# SwitchedPowerAdapter.net
KiCad netlist of a schematic drawn in EAGLE
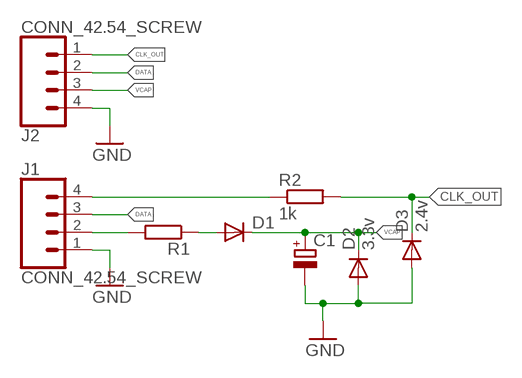
[diagram p0: schematic, sheet 1]

(export (version "E")
  (design (tool "Eeschema 10.0.6"))
  (components
    (comp (ref "C1")
      (value "CPOL-EUHL")
      (footprint "eagle-import:HL")
      (libsource (lib "eagle-import") (part "CPOL-EUHL"))
    )
    (comp (ref "D1")
      (value "DIODEDO-214AC")
      (footprint "eagle-import:DO214AC")
      (fields
        (field (name "DIGIKEY") "S1AFSCT-ND")
        (field (name "MF") "On Semiconductor")
        (field (name "MPN") "S1A")
      )
      (libsource (lib "eagle-import") (part "DIODEDO-214AC"))
    )
    (comp (ref "D2")
      (value "3.3v")
      (footprint "eagle-import:SOD-123")
      (fields (field (name "MF") "Vishay") (field (name "MPN") "MMSZ4683-HE3-08"))
      (libsource (lib "eagle-import") (part "DIODESOD-123"))
    )
    (comp (ref "D3")
      (value "2.4v")
      (footprint "eagle-import:SOD-123")
      (libsource (lib "eagle-import") (part "DIODESOD-123"))
    )
    (comp (ref "J1")
      (value "CONN_42.54_SCREW")
      (footprint "eagle-import:1X04_SCREW")
      (fields (field (name "MF") "On Shore") (field (name "MPN") "OSTVN04A150"))
      (libsource (lib "eagle-import") (part "CONN_42.54_SCREW"))
    )
    (comp (ref "J2")
      (value "CONN_42.54_SCREW")
      (footprint "eagle-import:1X04_SCREW")
      (fields (field (name "MF") "On Shore") (field (name "MPN") "OSTVN04A150"))
      (libsource (lib "eagle-import") (part "CONN_42.54_SCREW"))
    )
    (comp (ref "R1")
      (value "R-EU_R2512")
      (footprint "eagle-import:R2512")
      (libsource (lib "eagle-import") (part "R-EU_R2512"))
    )
    (comp (ref "R2")
      (value "1k")
      (footprint "eagle-import:R0402")
      (fields (field (name "MF") "Yageo"))
      (libsource (lib "eagle-import") (part "R-EU_R0402"))
    )
  )
  (nets
    (net (code "1") (name "CLK_OUT") (class "Default")
      (node (ref "D3") (pin "CAT") (pinfunction "C_CAT") (pintype "passive"))
      (node (ref "J2") (pin "1") (pinfunction "1_1") (pintype "passive"))
      (node (ref "R2") (pin "2") (pinfunction "2_2") (pintype "passive"))
    )
    (net (code "2") (name "DATA") (class "Default")
      (node (ref "J1") (pin "3") (pinfunction "3_3") (pintype "passive"))
      (node (ref "J2") (pin "2") (pinfunction "2_2") (pintype "passive"))
    )
    (net (code "3") (name "GND") (class "Default")
      (node (ref "C1") (pin "-") (pinfunction "-_-") (pintype "passive"))
      (node (ref "D2") (pin "ANODE") (pinfunction "A_ANODE") (pintype "passive"))
      (node (ref "D3") (pin "ANODE") (pinfunction "A_ANODE") (pintype "passive"))
      (node (ref "J1") (pin "1") (pinfunction "1_1") (pintype "passive"))
      (node (ref "J2") (pin "4") (pinfunction "4_4") (pintype "passive"))
    )
    (net (code "4") (name "Net-(D1-PadA)") (class "Default")
      (node (ref "D1") (pin "A") (pinfunction "A_A") (pintype "passive"))
      (node (ref "R1") (pin "1") (pinfunction "1_1") (pintype "passive"))
    )
    (net (code "5") (name "Net-(J1-Pad2)") (class "Default")
      (node (ref "J1") (pin "2") (pinfunction "2_2") (pintype "passive"))
      (node (ref "R1") (pin "2") (pinfunction "2_2") (pintype "passive"))
    )
    (net (code "6") (name "Net-(J1-Pad4)") (class "Default")
      (node (ref "J1") (pin "4") (pinfunction "4_4") (pintype "passive"))
      (node (ref "R2") (pin "1") (pinfunction "1_1") (pintype "passive"))
    )
    (net (code "7") (name "VCAP") (class "Default")
      (node (ref "C1") (pin "+") (pinfunction "+_+") (pintype "passive"))
      (node (ref "D1") (pin "C") (pinfunction "C_C") (pintype "passive"))
      (node (ref "D2") (pin "CAT") (pinfunction "C_CAT") (pintype "passive"))
      (node (ref "J2") (pin "3") (pinfunction "3_3") (pintype "passive"))
    )
  )
)
